# kingoftone_v1.net
KiCad netlist of a schematic drawn in EAGLE
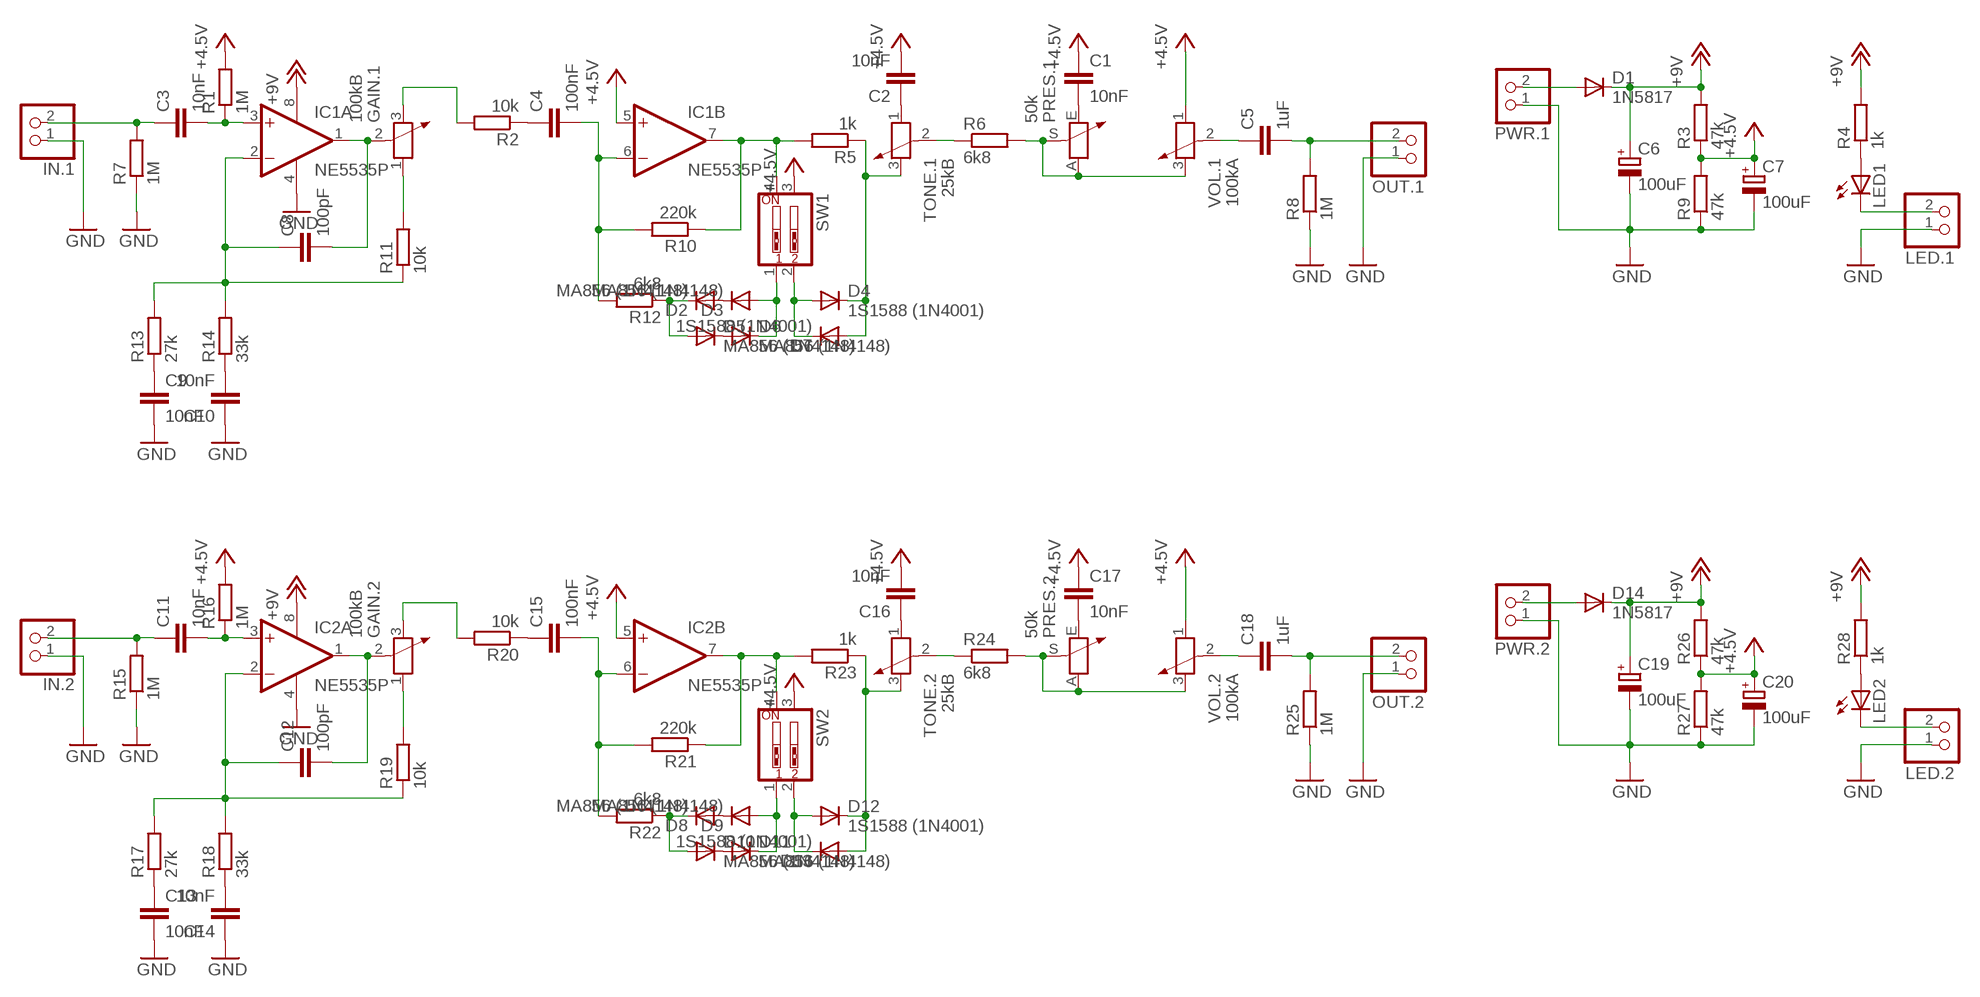
[diagram p0: schematic, sheet 1]

(export (version "E")
  (design (tool "Eeschema 10.0.6"))
  (components
    (comp (ref "C1")
      (value "10nF")
      (footprint "eagle-import:C050-025X075")
      (libsource (lib "eagle-import") (part "C-EU050-025X075"))
    )
    (comp (ref "C2")
      (value "10nF")
      (footprint "eagle-import:C050-025X075")
      (libsource (lib "eagle-import") (part "C-EU050-025X075"))
    )
    (comp (ref "C3")
      (value "10nF")
      (footprint "eagle-import:C050-025X075")
      (libsource (lib "eagle-import") (part "C-EU050-025X075"))
    )
    (comp (ref "C4")
      (value "100nF")
      (footprint "eagle-import:C050-025X075")
      (libsource (lib "eagle-import") (part "C-EU050-025X075"))
    )
    (comp (ref "C5")
      (value "1uF")
      (footprint "eagle-import:C050-025X075")
      (libsource (lib "eagle-import") (part "C-EU050-025X075"))
    )
    (comp (ref "C6")
      (value "100uF")
      (footprint "eagle-import:E2,5-6")
      (libsource (lib "eagle-import") (part "CPOL-EUE2.5-6"))
    )
    (comp (ref "C7")
      (value "100uF")
      (footprint "eagle-import:E2,5-6")
      (libsource (lib "eagle-import") (part "CPOL-EUE2.5-6"))
    )
    (comp (ref "C8")
      (value "100pF")
      (footprint "eagle-import:C050-025X075")
      (libsource (lib "eagle-import") (part "C-EU050-025X075"))
    )
    (comp (ref "C9")
      (value "10nF")
      (footprint "eagle-import:C050-025X075")
      (libsource (lib "eagle-import") (part "C-EU050-025X075"))
    )
    (comp (ref "C10")
      (value "10nF")
      (footprint "eagle-import:C050-025X075")
      (libsource (lib "eagle-import") (part "C-EU050-025X075"))
    )
    (comp (ref "C11")
      (value "10nF")
      (footprint "eagle-import:C050-025X075")
      (libsource (lib "eagle-import") (part "C-EU050-025X075"))
    )
    (comp (ref "C12")
      (value "100pF")
      (footprint "eagle-import:C050-025X075")
      (libsource (lib "eagle-import") (part "C-EU050-025X075"))
    )
    (comp (ref "C13")
      (value "10nF")
      (footprint "eagle-import:C050-025X075")
      (libsource (lib "eagle-import") (part "C-EU050-025X075"))
    )
    (comp (ref "C14")
      (value "10nF")
      (footprint "eagle-import:C050-025X075")
      (libsource (lib "eagle-import") (part "C-EU050-025X075"))
    )
    (comp (ref "C15")
      (value "100nF")
      (footprint "eagle-import:C050-025X075")
      (libsource (lib "eagle-import") (part "C-EU050-025X075"))
    )
    (comp (ref "C16")
      (value "10nF")
      (footprint "eagle-import:C050-025X075")
      (libsource (lib "eagle-import") (part "C-EU050-025X075"))
    )
    (comp (ref "C17")
      (value "10nF")
      (footprint "eagle-import:C050-025X075")
      (libsource (lib "eagle-import") (part "C-EU050-025X075"))
    )
    (comp (ref "C18")
      (value "1uF")
      (footprint "eagle-import:C050-025X075")
      (libsource (lib "eagle-import") (part "C-EU050-025X075"))
    )
    (comp (ref "C19")
      (value "100uF")
      (footprint "eagle-import:E2,5-6")
      (libsource (lib "eagle-import") (part "CPOL-EUE2.5-6"))
    )
    (comp (ref "C20")
      (value "100uF")
      (footprint "eagle-import:E2,5-6")
      (libsource (lib "eagle-import") (part "CPOL-EUE2.5-6"))
    )
    (comp (ref "D1")
      (value "1N5817")
      (footprint "eagle-import:DO41-5")
      (libsource (lib "eagle-import") (part "1N4004C"))
    )
    (comp (ref "D2")
      (value "MA856 (1N4148)")
      (footprint "eagle-import:DO41-5")
      (libsource (lib "eagle-import") (part "1N4004C"))
    )
    (comp (ref "D3")
      (value "MA856 (1N4148)")
      (footprint "eagle-import:DO41-5")
      (libsource (lib "eagle-import") (part "1N4004C"))
    )
    (comp (ref "D4")
      (value "1S1588 (1N4001)")
      (footprint "eagle-import:DO41-5")
      (libsource (lib "eagle-import") (part "1N4004C"))
    )
    (comp (ref "D5")
      (value "MA856 (1N4148)")
      (footprint "eagle-import:DO41-5")
      (libsource (lib "eagle-import") (part "1N4004C"))
    )
    (comp (ref "D6")
      (value "MA856 (1N4148)")
      (footprint "eagle-import:DO41-5")
      (libsource (lib "eagle-import") (part "1N4004C"))
    )
    (comp (ref "D7")
      (value "1S1588 (1N4001)")
      (footprint "eagle-import:DO41-5")
      (libsource (lib "eagle-import") (part "1N4004C"))
    )
    (comp (ref "D8")
      (value "MA856 (1N4148)")
      (footprint "eagle-import:DO41-5")
      (libsource (lib "eagle-import") (part "1N4004C"))
    )
    (comp (ref "D9")
      (value "MA856 (1N4148)")
      (footprint "eagle-import:DO41-5")
      (libsource (lib "eagle-import") (part "1N4004C"))
    )
    (comp (ref "D10")
      (value "MA856 (1N4148)")
      (footprint "eagle-import:DO41-5")
      (libsource (lib "eagle-import") (part "1N4004C"))
    )
    (comp (ref "D11")
      (value "MA856 (1N4148)")
      (footprint "eagle-import:DO41-5")
      (libsource (lib "eagle-import") (part "1N4004C"))
    )
    (comp (ref "D12")
      (value "1S1588 (1N4001)")
      (footprint "eagle-import:DO41-5")
      (libsource (lib "eagle-import") (part "1N4004C"))
    )
    (comp (ref "D13")
      (value "1S1588 (1N4001)")
      (footprint "eagle-import:DO41-5")
      (libsource (lib "eagle-import") (part "1N4004C"))
    )
    (comp (ref "D14")
      (value "1N5817")
      (footprint "eagle-import:DO41-5")
      (libsource (lib "eagle-import") (part "1N4004C"))
    )
    (comp (ref "GAIN.1")
      (value "100kB")
      (footprint "eagle-import:1X03")
      (libsource (lib "eagle-import") (part "POTENTIOMETER_"))
    )
    (comp (ref "GAIN.2")
      (value "100kB")
      (footprint "eagle-import:1X03")
      (libsource (lib "eagle-import") (part "POTENTIOMETER_"))
    )
    (comp (ref "IC1")
      (value "NE5535P")
      (footprint "eagle-import:DIL08")
      (libsource (lib "eagle-import") (part "NE5535P"))
    )
    (comp (ref "IC2")
      (value "NE5535P")
      (footprint "eagle-import:DIL08")
      (libsource (lib "eagle-import") (part "NE5535P"))
    )
    (comp (ref "IN.1")
      (value "PINHD-1X2")
      (footprint "eagle-import:1X02")
      (libsource (lib "eagle-import") (part "PINHD-1X2"))
    )
    (comp (ref "IN.2")
      (value "PINHD-1X2")
      (footprint "eagle-import:1X02")
      (libsource (lib "eagle-import") (part "PINHD-1X2"))
    )
    (comp (ref "LED.1")
      (value "PINHD-1X2")
      (footprint "eagle-import:1X02")
      (libsource (lib "eagle-import") (part "PINHD-1X2"))
    )
    (comp (ref "LED.2")
      (value "PINHD-1X2")
      (footprint "eagle-import:1X02")
      (libsource (lib "eagle-import") (part "PINHD-1X2"))
    )
    (comp (ref "LED1")
      (value "LED3MM")
      (footprint "eagle-import:LED3MM")
      (libsource (lib "eagle-import") (part "LED3MM"))
    )
    (comp (ref "LED2")
      (value "LED3MM")
      (footprint "eagle-import:LED3MM")
      (libsource (lib "eagle-import") (part "LED3MM"))
    )
    (comp (ref "OUT.1")
      (value "PINHD-1X2")
      (footprint "eagle-import:1X02")
      (libsource (lib "eagle-import") (part "PINHD-1X2"))
    )
    (comp (ref "OUT.2")
      (value "PINHD-1X2")
      (footprint "eagle-import:1X02")
      (libsource (lib "eagle-import") (part "PINHD-1X2"))
    )
    (comp (ref "PRES.1")
      (value "50k")
      (footprint "eagle-import:CT6")
      (libsource (lib "eagle-import") (part "POTENTIOMETER_CT6"))
    )
    (comp (ref "PRES.2")
      (value "50k")
      (footprint "eagle-import:CT6")
      (libsource (lib "eagle-import") (part "POTENTIOMETER_CT6"))
    )
    (comp (ref "PWR.1")
      (value "PINHD-1X2")
      (footprint "eagle-import:1X02")
      (libsource (lib "eagle-import") (part "PINHD-1X2"))
    )
    (comp (ref "PWR.2")
      (value "PINHD-1X2")
      (footprint "eagle-import:1X02")
      (libsource (lib "eagle-import") (part "PINHD-1X2"))
    )
    (comp (ref "R1")
      (value "1M")
      (footprint "eagle-import:0207_5V")
      (libsource (lib "eagle-import") (part "R-EU_0207/5V"))
    )
    (comp (ref "R2")
      (value "10k")
      (footprint "eagle-import:0207_5V")
      (libsource (lib "eagle-import") (part "R-EU_0207/5V"))
    )
    (comp (ref "R3")
      (value "47k")
      (footprint "eagle-import:0207_5V")
      (libsource (lib "eagle-import") (part "R-EU_0207/5V"))
    )
    (comp (ref "R4")
      (value "1k")
      (footprint "eagle-import:0207_5V")
      (libsource (lib "eagle-import") (part "R-EU_0207/5V"))
    )
    (comp (ref "R5")
      (value "1k")
      (footprint "eagle-import:0207_5V")
      (libsource (lib "eagle-import") (part "R-EU_0207/5V"))
    )
    (comp (ref "R6")
      (value "6k8")
      (footprint "eagle-import:0207_5V")
      (libsource (lib "eagle-import") (part "R-EU_0207/5V"))
    )
    (comp (ref "R7")
      (value "1M")
      (footprint "eagle-import:0207_5V")
      (libsource (lib "eagle-import") (part "R-EU_0207/5V"))
    )
    (comp (ref "R8")
      (value "1M")
      (footprint "eagle-import:0207_5V")
      (libsource (lib "eagle-import") (part "R-EU_0207/5V"))
    )
    (comp (ref "R9")
      (value "47k")
      (footprint "eagle-import:0207_5V")
      (libsource (lib "eagle-import") (part "R-EU_0207/5V"))
    )
    (comp (ref "R10")
      (value "220k")
      (footprint "eagle-import:0207_5V")
      (libsource (lib "eagle-import") (part "R-EU_0207/5V"))
    )
    (comp (ref "R11")
      (value "10k")
      (footprint "eagle-import:0207_5V")
      (libsource (lib "eagle-import") (part "R-EU_0207/5V"))
    )
    (comp (ref "R12")
      (value "6k8")
      (footprint "eagle-import:0207_5V")
      (libsource (lib "eagle-import") (part "R-EU_0207/5V"))
    )
    (comp (ref "R13")
      (value "27k")
      (footprint "eagle-import:0207_5V")
      (libsource (lib "eagle-import") (part "R-EU_0207/5V"))
    )
    (comp (ref "R14")
      (value "33k")
      (footprint "eagle-import:0207_5V")
      (libsource (lib "eagle-import") (part "R-EU_0207/5V"))
    )
    (comp (ref "R15")
      (value "1M")
      (footprint "eagle-import:0207_5V")
      (libsource (lib "eagle-import") (part "R-EU_0207/5V"))
    )
    (comp (ref "R16")
      (value "1M")
      (footprint "eagle-import:0207_5V")
      (libsource (lib "eagle-import") (part "R-EU_0207/5V"))
    )
    (comp (ref "R17")
      (value "27k")
      (footprint "eagle-import:0207_5V")
      (libsource (lib "eagle-import") (part "R-EU_0207/5V"))
    )
    (comp (ref "R18")
      (value "33k")
      (footprint "eagle-import:0207_5V")
      (libsource (lib "eagle-import") (part "R-EU_0207/5V"))
    )
    (comp (ref "R19")
      (value "10k")
      (footprint "eagle-import:0207_5V")
      (libsource (lib "eagle-import") (part "R-EU_0207/5V"))
    )
    (comp (ref "R20")
      (value "10k")
      (footprint "eagle-import:0207_5V")
      (libsource (lib "eagle-import") (part "R-EU_0207/5V"))
    )
    (comp (ref "R21")
      (value "220k")
      (footprint "eagle-import:0207_5V")
      (libsource (lib "eagle-import") (part "R-EU_0207/5V"))
    )
    (comp (ref "R22")
      (value "6k8")
      (footprint "eagle-import:0207_5V")
      (libsource (lib "eagle-import") (part "R-EU_0207/5V"))
    )
    (comp (ref "R23")
      (value "1k")
      (footprint "eagle-import:0207_5V")
      (libsource (lib "eagle-import") (part "R-EU_0207/5V"))
    )
    (comp (ref "R24")
      (value "6k8")
      (footprint "eagle-import:0207_5V")
      (libsource (lib "eagle-import") (part "R-EU_0207/5V"))
    )
    (comp (ref "R25")
      (value "1M")
      (footprint "eagle-import:0207_5V")
      (libsource (lib "eagle-import") (part "R-EU_0207/5V"))
    )
    (comp (ref "R26")
      (value "47k")
      (footprint "eagle-import:0207_5V")
      (libsource (lib "eagle-import") (part "R-EU_0207/5V"))
    )
    (comp (ref "R27")
      (value "47k")
      (footprint "eagle-import:0207_5V")
      (libsource (lib "eagle-import") (part "R-EU_0207/5V"))
    )
    (comp (ref "R28")
      (value "1k")
      (footprint "eagle-import:0207_5V")
      (libsource (lib "eagle-import") (part "R-EU_0207/5V"))
    )
    (comp (ref "SW1")
      (value "SW_DIP-2")
      (footprint "eagle-import:EDG-02")
      (libsource (lib "eagle-import") (part "SW_DIP-2"))
    )
    (comp (ref "SW2")
      (value "SW_DIP-2")
      (footprint "eagle-import:EDG-02")
      (libsource (lib "eagle-import") (part "SW_DIP-2"))
    )
    (comp (ref "TONE.1")
      (value "25kB")
      (footprint "eagle-import:1X03")
      (libsource (lib "eagle-import") (part "POTENTIOMETER_"))
    )
    (comp (ref "TONE.2")
      (value "25kB")
      (footprint "eagle-import:1X03")
      (libsource (lib "eagle-import") (part "POTENTIOMETER_"))
    )
    (comp (ref "VOL.1")
      (value "100kA")
      (footprint "eagle-import:1X03")
      (libsource (lib "eagle-import") (part "POTENTIOMETER_"))
    )
    (comp (ref "VOL.2")
      (value "100kA")
      (footprint "eagle-import:1X03")
      (libsource (lib "eagle-import") (part "POTENTIOMETER_"))
    )
  )
  (nets
    (net (code "1") (name "+4.5V") (class "Default")
      (node (ref "C1") (pin "1") (pinfunction "1_1") (pintype "passive"))
      (node (ref "C16") (pin "2") (pinfunction "2_2") (pintype "passive"))
      (node (ref "C17") (pin "1") (pinfunction "1_1") (pintype "passive"))
      (node (ref "C2") (pin "2") (pinfunction "2_2") (pintype "passive"))
      (node (ref "C20") (pin "+") (pinfunction "+_+") (pintype "passive"))
      (node (ref "C7") (pin "+") (pinfunction "+_+") (pintype "passive"))
      (node (ref "IC1") (pin "5") (pinfunction "+IN_5") (pintype "input"))
      (node (ref "IC2") (pin "5") (pinfunction "+IN_5") (pintype "input"))
      (node (ref "R1") (pin "2") (pinfunction "2_2") (pintype "passive"))
      (node (ref "R16") (pin "2") (pinfunction "2_2") (pintype "passive"))
      (node (ref "R26") (pin "1") (pinfunction "1_1") (pintype "passive"))
      (node (ref "R27") (pin "2") (pinfunction "2_2") (pintype "passive"))
      (node (ref "R3") (pin "1") (pinfunction "1_1") (pintype "passive"))
      (node (ref "R9") (pin "2") (pinfunction "2_2") (pintype "passive"))
      (node (ref "SW1") (pin "3") (pinfunction "3_3") (pintype "passive"))
      (node (ref "SW2") (pin "3") (pinfunction "3_3") (pintype "passive"))
      (node (ref "VOL.1") (pin "1") (pinfunction "1_1") (pintype "passive"))
      (node (ref "VOL.2") (pin "1") (pinfunction "1_1") (pintype "passive"))
    )
    (net (code "2") (name "+9V") (class "Default")
      (node (ref "C19") (pin "+") (pinfunction "+_+") (pintype "passive"))
      (node (ref "C6") (pin "+") (pinfunction "+_+") (pintype "passive"))
      (node (ref "D1") (pin "C") (pinfunction "C_C") (pintype "passive"))
      (node (ref "D14") (pin "C") (pinfunction "C_C") (pintype "passive"))
      (node (ref "IC1") (pin "8") (pinfunction "V+_8") (pintype "power_in"))
      (node (ref "IC2") (pin "8") (pinfunction "V+_8") (pintype "power_in"))
      (node (ref "R26") (pin "2") (pinfunction "2_2") (pintype "passive"))
      (node (ref "R28") (pin "2") (pinfunction "2_2") (pintype "passive"))
      (node (ref "R3") (pin "2") (pinfunction "2_2") (pintype "passive"))
      (node (ref "R4") (pin "2") (pinfunction "2_2") (pintype "passive"))
    )
    (net (code "3") (name "GND") (class "Default")
      (node (ref "C10") (pin "1") (pinfunction "1_1") (pintype "passive"))
      (node (ref "C13") (pin "2") (pinfunction "2_2") (pintype "passive"))
      (node (ref "C14") (pin "1") (pinfunction "1_1") (pintype "passive"))
      (node (ref "C19") (pin "-") (pinfunction "-_-") (pintype "passive"))
      (node (ref "C20") (pin "-") (pinfunction "-_-") (pintype "passive"))
      (node (ref "C6") (pin "-") (pinfunction "-_-") (pintype "passive"))
      (node (ref "C7") (pin "-") (pinfunction "-_-") (pintype "passive"))
      (node (ref "C9") (pin "2") (pinfunction "2_2") (pintype "passive"))
      (node (ref "IC1") (pin "4") (pinfunction "V-_4") (pintype "power_in"))
      (node (ref "IC2") (pin "4") (pinfunction "V-_4") (pintype "power_in"))
      (node (ref "IN.1") (pin "1") (pinfunction "1_1") (pintype "passive"))
      (node (ref "IN.2") (pin "1") (pinfunction "1_1") (pintype "passive"))
      (node (ref "LED.1") (pin "1") (pinfunction "1_1") (pintype "passive"))
      (node (ref "LED.2") (pin "1") (pinfunction "1_1") (pintype "passive"))
      (node (ref "OUT.1") (pin "1") (pinfunction "1_1") (pintype "passive"))
      (node (ref "OUT.2") (pin "1") (pinfunction "1_1") (pintype "passive"))
      (node (ref "PWR.1") (pin "1") (pinfunction "1_1") (pintype "passive"))
      (node (ref "PWR.2") (pin "1") (pinfunction "1_1") (pintype "passive"))
      (node (ref "R15") (pin "1") (pinfunction "1_1") (pintype "passive"))
      (node (ref "R25") (pin "1") (pinfunction "1_1") (pintype "passive"))
      (node (ref "R27") (pin "1") (pinfunction "1_1") (pintype "passive"))
      (node (ref "R7") (pin "1") (pinfunction "1_1") (pintype "passive"))
      (node (ref "R8") (pin "1") (pinfunction "1_1") (pintype "passive"))
      (node (ref "R9") (pin "1") (pinfunction "1_1") (pintype "passive"))
    )
    (net (code "4") (name "Net-(C2-Pad1)") (class "Default")
      (node (ref "C2") (pin "1") (pinfunction "1_1") (pintype "passive"))
      (node (ref "TONE.1") (pin "1") (pinfunction "1_1") (pintype "passive"))
    )
    (net (code "5") (name "Net-(C3-Pad1)") (class "Default")
      (node (ref "C3") (pin "1") (pinfunction "1_1") (pintype "passive"))
      (node (ref "IN.1") (pin "2") (pinfunction "2_2") (pintype "passive"))
      (node (ref "R7") (pin "2") (pinfunction "2_2") (pintype "passive"))
    )
    (net (code "6") (name "Net-(C4-Pad1)") (class "Default")
      (node (ref "C4") (pin "1") (pinfunction "1_1") (pintype "passive"))
      (node (ref "R2") (pin "1") (pinfunction "1_1") (pintype "passive"))
    )
    (net (code "7") (name "Net-(C5-Pad2)") (class "Default")
      (node (ref "C5") (pin "2") (pinfunction "2_2") (pintype "passive"))
      (node (ref "OUT.1") (pin "2") (pinfunction "2_2") (pintype "passive"))
      (node (ref "R8") (pin "2") (pinfunction "2_2") (pintype "passive"))
    )
    (net (code "8") (name "Net-(C9-Pad1)") (class "Default")
      (node (ref "C9") (pin "1") (pinfunction "1_1") (pintype "passive"))
      (node (ref "R13") (pin "1") (pinfunction "1_1") (pintype "passive"))
    )
    (net (code "9") (name "Net-(C10-Pad2)") (class "Default")
      (node (ref "C10") (pin "2") (pinfunction "2_2") (pintype "passive"))
      (node (ref "R14") (pin "1") (pinfunction "1_1") (pintype "passive"))
    )
    (net (code "10") (name "Net-(C11-Pad1)") (class "Default")
      (node (ref "C11") (pin "1") (pinfunction "1_1") (pintype "passive"))
      (node (ref "IN.2") (pin "2") (pinfunction "2_2") (pintype "passive"))
      (node (ref "R15") (pin "2") (pinfunction "2_2") (pintype "passive"))
    )
    (net (code "11") (name "Net-(C13-Pad1)") (class "Default")
      (node (ref "C13") (pin "1") (pinfunction "1_1") (pintype "passive"))
      (node (ref "R17") (pin "1") (pinfunction "1_1") (pintype "passive"))
    )
    (net (code "12") (name "Net-(C14-Pad2)") (class "Default")
      (node (ref "C14") (pin "2") (pinfunction "2_2") (pintype "passive"))
      (node (ref "R18") (pin "1") (pinfunction "1_1") (pintype "passive"))
    )
    (net (code "13") (name "Net-(C15-Pad1)") (class "Default")
      (node (ref "C15") (pin "1") (pinfunction "1_1") (pintype "passive"))
      (node (ref "R20") (pin "1") (pinfunction "1_1") (pintype "passive"))
    )
    (net (code "14") (name "Net-(C16-Pad1)") (class "Default")
      (node (ref "C16") (pin "1") (pinfunction "1_1") (pintype "passive"))
      (node (ref "TONE.2") (pin "1") (pinfunction "1_1") (pintype "passive"))
    )
    (net (code "15") (name "Net-(C18-Pad2)") (class "Default")
      (node (ref "C18") (pin "2") (pinfunction "2_2") (pintype "passive"))
      (node (ref "OUT.2") (pin "2") (pinfunction "2_2") (pintype "passive"))
      (node (ref "R25") (pin "2") (pinfunction "2_2") (pintype "passive"))
    )
    (net (code "16") (name "Net-(D1-PadA)") (class "Default")
      (node (ref "D1") (pin "A") (pinfunction "A_A") (pintype "passive"))
      (node (ref "PWR.1") (pin "2") (pinfunction "2_2") (pintype "passive"))
    )
    (net (code "17") (name "Net-(D2-PadA)") (class "Default")
      (node (ref "D2") (pin "A") (pinfunction "A_A") (pintype "passive"))
      (node (ref "D3") (pin "C") (pinfunction "C_C") (pintype "passive"))
    )
    (net (code "18") (name "Net-(D2-PadC)") (class "Default")
      (node (ref "D2") (pin "C") (pinfunction "C_C") (pintype "passive"))
      (node (ref "D5") (pin "A") (pinfunction "A_A") (pintype "passive"))
      (node (ref "R12") (pin "1") (pinfunction "1_1") (pintype "passive"))
    )
    (net (code "19") (name "Net-(D3-PadA)") (class "Default")
      (node (ref "D3") (pin "A") (pinfunction "A_A") (pintype "passive"))
      (node (ref "D6") (pin "C") (pinfunction "C_C") (pintype "passive"))
      (node (ref "SW1") (pin "1") (pinfunction "1_1") (pintype "passive"))
    )
    (net (code "20") (name "Net-(D4-PadA)") (class "Default")
      (node (ref "D4") (pin "A") (pinfunction "A_A") (pintype "passive"))
      (node (ref "D7") (pin "C") (pinfunction "C_C") (pintype "passive"))
      (node (ref "SW1") (pin "2") (pinfunction "2_2") (pintype "passive"))
    )
    (net (code "21") (name "Net-(D5-PadC)") (class "Default")
      (node (ref "D5") (pin "C") (pinfunction "C_C") (pintype "passive"))
      (node (ref "D6") (pin "A") (pinfunction "A_A") (pintype "passive"))
    )
    (net (code "22") (name "Net-(D8-PadA)") (class "Default")
      (node (ref "D8") (pin "A") (pinfunction "A_A") (pintype "passive"))
      (node (ref "D9") (pin "C") (pinfunction "C_C") (pintype "passive"))
    )
    (net (code "23") (name "Net-(D10-PadA)") (class "Default")
      (node (ref "D10") (pin "A") (pinfunction "A_A") (pintype "passive"))
      (node (ref "D8") (pin "C") (pinfunction "C_C") (pintype "passive"))
      (node (ref "R22") (pin "1") (pinfunction "1_1") (pintype "passive"))
    )
    (net (code "24") (name "Net-(D10-PadC)") (class "Default")
      (node (ref "D10") (pin "C") (pinfunction "C_C") (pintype "passive"))
      (node (ref "D11") (pin "A") (pinfunction "A_A") (pintype "passive"))
    )
    (net (code "25") (name "Net-(D11-PadC)") (class "Default")
      (node (ref "D11") (pin "C") (pinfunction "C_C") (pintype "passive"))
      (node (ref "D9") (pin "A") (pinfunction "A_A") (pintype "passive"))
      (node (ref "SW2") (pin "1") (pinfunction "1_1") (pintype "passive"))
    )
    (net (code "26") (name "Net-(D12-PadA)") (class "Default")
      (node (ref "D12") (pin "A") (pinfunction "A_A") (pintype "passive"))
      (node (ref "D13") (pin "C") (pinfunction "C_C") (pintype "passive"))
      (node (ref "SW2") (pin "2") (pinfunction "2_2") (pintype "passive"))
    )
    (net (code "27") (name "Net-(D14-PadA)") (class "Default")
      (node (ref "D14") (pin "A") (pinfunction "A_A") (pintype "passive"))
      (node (ref "PWR.2") (pin "2") (pinfunction "2_2") (pintype "passive"))
    )
    (net (code "28") (name "Net-(GAIN.1-2)") (class "Default")
      (node (ref "GAIN.1") (pin "3") (pinfunction "2_3") (pintype "passive"))
      (node (ref "R2") (pin "2") (pinfunction "2_2") (pintype "passive"))
    )
    (net (code "29") (name "Net-(GAIN.1-3)") (class "Default")
      (node (ref "C8") (pin "2") (pinfunction "2_2") (pintype "passive"))
      (node (ref "GAIN.1") (pin "2") (pinfunction "3_2") (pintype "passive"))
      (node (ref "IC1") (pin "1") (pinfunction "OUT_1") (pintype "output"))
    )
    (net (code "30") (name "Net-(GAIN.1-Pad1)") (class "Default")
      (node (ref "GAIN.1") (pin "1") (pinfunction "1_1") (pintype "passive"))
      (node (ref "R11") (pin "2") (pinfunction "2_2") (pintype "passive"))
    )
    (net (code "31") (name "Net-(GAIN.2-2)") (class "Default")
      (node (ref "GAIN.2") (pin "3") (pinfunction "2_3") (pintype "passive"))
      (node (ref "R20") (pin "2") (pinfunction "2_2") (pintype "passive"))
    )
    (net (code "32") (name "Net-(GAIN.2-3)") (class "Default")
      (node (ref "C12") (pin "2") (pinfunction "2_2") (pintype "passive"))
      (node (ref "GAIN.2") (pin "2") (pinfunction "3_2") (pintype "passive"))
      (node (ref "IC2") (pin "1") (pinfunction "OUT_1") (pintype "output"))
    )
    (net (code "33") (name "Net-(GAIN.2-Pad1)") (class "Default")
      (node (ref "GAIN.2") (pin "1") (pinfunction "1_1") (pintype "passive"))
      (node (ref "R19") (pin "2") (pinfunction "2_2") (pintype "passive"))
    )
    (net (code "34") (name "Net-(IC1A-+IN)") (class "Default")
      (node (ref "C3") (pin "2") (pinfunction "2_2") (pintype "passive"))
      (node (ref "IC1") (pin "3") (pinfunction "+IN_3") (pintype "input"))
      (node (ref "R1") (pin "1") (pinfunction "1_1") (pintype "passive"))
    )
    (net (code "35") (name "Net-(IC1A--IN)") (class "Default")
      (node (ref "C8") (pin "1") (pinfunction "1_1") (pintype "passive"))
      (node (ref "IC1") (pin "2") (pinfunction "-IN_2") (pintype "input"))
      (node (ref "R11") (pin "1") (pinfunction "1_1") (pintype "passive"))
      (node (ref "R13") (pin "2") (pinfunction "2_2") (pintype "passive"))
      (node (ref "R14") (pin "2") (pinfunction "2_2") (pintype "passive"))
    )
    (net (code "36") (name "Net-(IC1B--IN)") (class "Default")
      (node (ref "C4") (pin "2") (pinfunction "2_2") (pintype "passive"))
      (node (ref "IC1") (pin "6") (pinfunction "-IN_6") (pintype "input"))
      (node (ref "R10") (pin "2") (pinfunction "2_2") (pintype "passive"))
      (node (ref "R12") (pin "2") (pinfunction "2_2") (pintype "passive"))
    )
    (net (code "37") (name "Net-(IC1B-OUT)") (class "Default")
      (node (ref "IC1") (pin "7") (pinfunction "OUT_7") (pintype "output"))
      (node (ref "R10") (pin "1") (pinfunction "1_1") (pintype "passive"))
      (node (ref "R5") (pin "2") (pinfunction "2_2") (pintype "passive"))
      (node (ref "SW1") (pin "4") (pinfunction "4_4") (pintype "passive"))
    )
    (net (code "38") (name "Net-(IC2A-+IN)") (class "Default")
      (node (ref "C11") (pin "2") (pinfunction "2_2") (pintype "passive"))
      (node (ref "IC2") (pin "3") (pinfunction "+IN_3") (pintype "input"))
      (node (ref "R16") (pin "1") (pinfunction "1_1") (pintype "passive"))
    )
    (net (code "39") (name "Net-(IC2A--IN)") (class "Default")
      (node (ref "C12") (pin "1") (pinfunction "1_1") (pintype "passive"))
      (node (ref "IC2") (pin "2") (pinfunction "-IN_2") (pintype "input"))
      (node (ref "R17") (pin "2") (pinfunction "2_2") (pintype "passive"))
      (node (ref "R18") (pin "2") (pinfunction "2_2") (pintype "passive"))
      (node (ref "R19") (pin "1") (pinfunction "1_1") (pintype "passive"))
    )
    (net (code "40") (name "Net-(IC2B--IN)") (class "Default")
      (node (ref "C15") (pin "2") (pinfunction "2_2") (pintype "passive"))
      (node (ref "IC2") (pin "6") (pinfunction "-IN_6") (pintype "input"))
      (node (ref "R21") (pin "2") (pinfunction "2_2") (pintype "passive"))
      (node (ref "R22") (pin "2") (pinfunction "2_2") (pintype "passive"))
    )
    (net (code "41") (name "Net-(IC2B-OUT)") (class "Default")
      (node (ref "IC2") (pin "7") (pinfunction "OUT_7") (pintype "output"))
      (node (ref "R21") (pin "1") (pinfunction "1_1") (pintype "passive"))
      (node (ref "R23") (pin "2") (pinfunction "2_2") (pintype "passive"))
      (node (ref "SW2") (pin "4") (pinfunction "4_4") (pintype "passive"))
    )
    (net (code "42") (name "Net-(LED1-C)") (class "Default")
      (node (ref "LED.1") (pin "2") (pinfunction "2_2") (pintype "passive"))
      (node (ref "LED1") (pin "K") (pinfunction "C_K") (pintype "passive"))
    )
    (net (code "43") (name "Net-(LED1-PadA)") (class "Default")
      (node (ref "LED1") (pin "A") (pinfunction "A_A") (pintype "passive"))
      (node (ref "R4") (pin "1") (pinfunction "1_1") (pintype "passive"))
    )
    (net (code "44") (name "Net-(LED2-C)") (class "Default")
      (node (ref "LED.2") (pin "2") (pinfunction "2_2") (pintype "passive"))
      (node (ref "LED2") (pin "K") (pinfunction "C_K") (pintype "passive"))
    )
    (net (code "45") (name "Net-(LED2-PadA)") (class "Default")
      (node (ref "LED2") (pin "A") (pinfunction "A_A") (pintype "passive"))
      (node (ref "R28") (pin "1") (pinfunction "1_1") (pintype "passive"))
    )
    (net (code "46") (name "Net-(PRES.1-1)") (class "Default")
      (node (ref "PRES.1") (pin "A") (pinfunction "1_A") (pintype "passive"))
      (node (ref "PRES.1") (pin "S") (pinfunction "3_S") (pintype "passive"))
      (node (ref "R6") (pin "2") (pinfunction "2_2") (pintype "passive"))
      (node (ref "VOL.1") (pin "3") (pinfunction "2_3") (pintype "passive"))
    )
    (net (code "47") (name "Net-(PRES.1-2)") (class "Default")
      (node (ref "C1") (pin "2") (pinfunction "2_2") (pintype "passive"))
      (node (ref "PRES.1") (pin "E") (pinfunction "2_E") (pintype "passive"))
    )
    (net (code "48") (name "Net-(PRES.2-1)") (class "Default")
      (node (ref "PRES.2") (pin "A") (pinfunction "1_A") (pintype "passive"))
      (node (ref "PRES.2") (pin "S") (pinfunction "3_S") (pintype "passive"))
      (node (ref "R24") (pin "2") (pinfunction "2_2") (pintype "passive"))
      (node (ref "VOL.2") (pin "3") (pinfunction "2_3") (pintype "passive"))
    )
    (net (code "49") (name "Net-(PRES.2-2)") (class "Default")
      (node (ref "C17") (pin "2") (pinfunction "2_2") (pintype "passive"))
      (node (ref "PRES.2") (pin "E") (pinfunction "2_E") (pintype "passive"))
    )
    (net (code "50") (name "Net-(TONE.1-2)") (class "Default")
      (node (ref "D4") (pin "C") (pinfunction "C_C") (pintype "passive"))
      (node (ref "D7") (pin "A") (pinfunction "A_A") (pintype "passive"))
      (node (ref "R5") (pin "1") (pinfunction "1_1") (pintype "passive"))
      (node (ref "TONE.1") (pin "3") (pinfunction "2_3") (pintype "passive"))
    )
    (net (code "51") (name "Net-(TONE.1-3)") (class "Default")
      (node (ref "R6") (pin "1") (pinfunction "1_1") (pintype "passive"))
      (node (ref "TONE.1") (pin "2") (pinfunction "3_2") (pintype "passive"))
    )
    (net (code "52") (name "Net-(TONE.2-2)") (class "Default")
      (node (ref "D12") (pin "C") (pinfunction "C_C") (pintype "passive"))
      (node (ref "D13") (pin "A") (pinfunction "A_A") (pintype "passive"))
      (node (ref "R23") (pin "1") (pinfunction "1_1") (pintype "passive"))
      (node (ref "TONE.2") (pin "3") (pinfunction "2_3") (pintype "passive"))
    )
    (net (code "53") (name "Net-(TONE.2-3)") (class "Default")
      (node (ref "R24") (pin "1") (pinfunction "1_1") (pintype "passive"))
      (node (ref "TONE.2") (pin "2") (pinfunction "3_2") (pintype "passive"))
    )
    (net (code "54") (name "Net-(VOL.1-3)") (class "Default")
      (node (ref "C5") (pin "1") (pinfunction "1_1") (pintype "passive"))
      (node (ref "VOL.1") (pin "2") (pinfunction "3_2") (pintype "passive"))
    )
    (net (code "55") (name "Net-(VOL.2-3)") (class "Default")
      (node (ref "C18") (pin "1") (pinfunction "1_1") (pintype "passive"))
      (node (ref "VOL.2") (pin "2") (pinfunction "3_2") (pintype "passive"))
    )
  )
)
